# Sheet1.net
KiCad netlist of a schematic drawn in Altium Designer
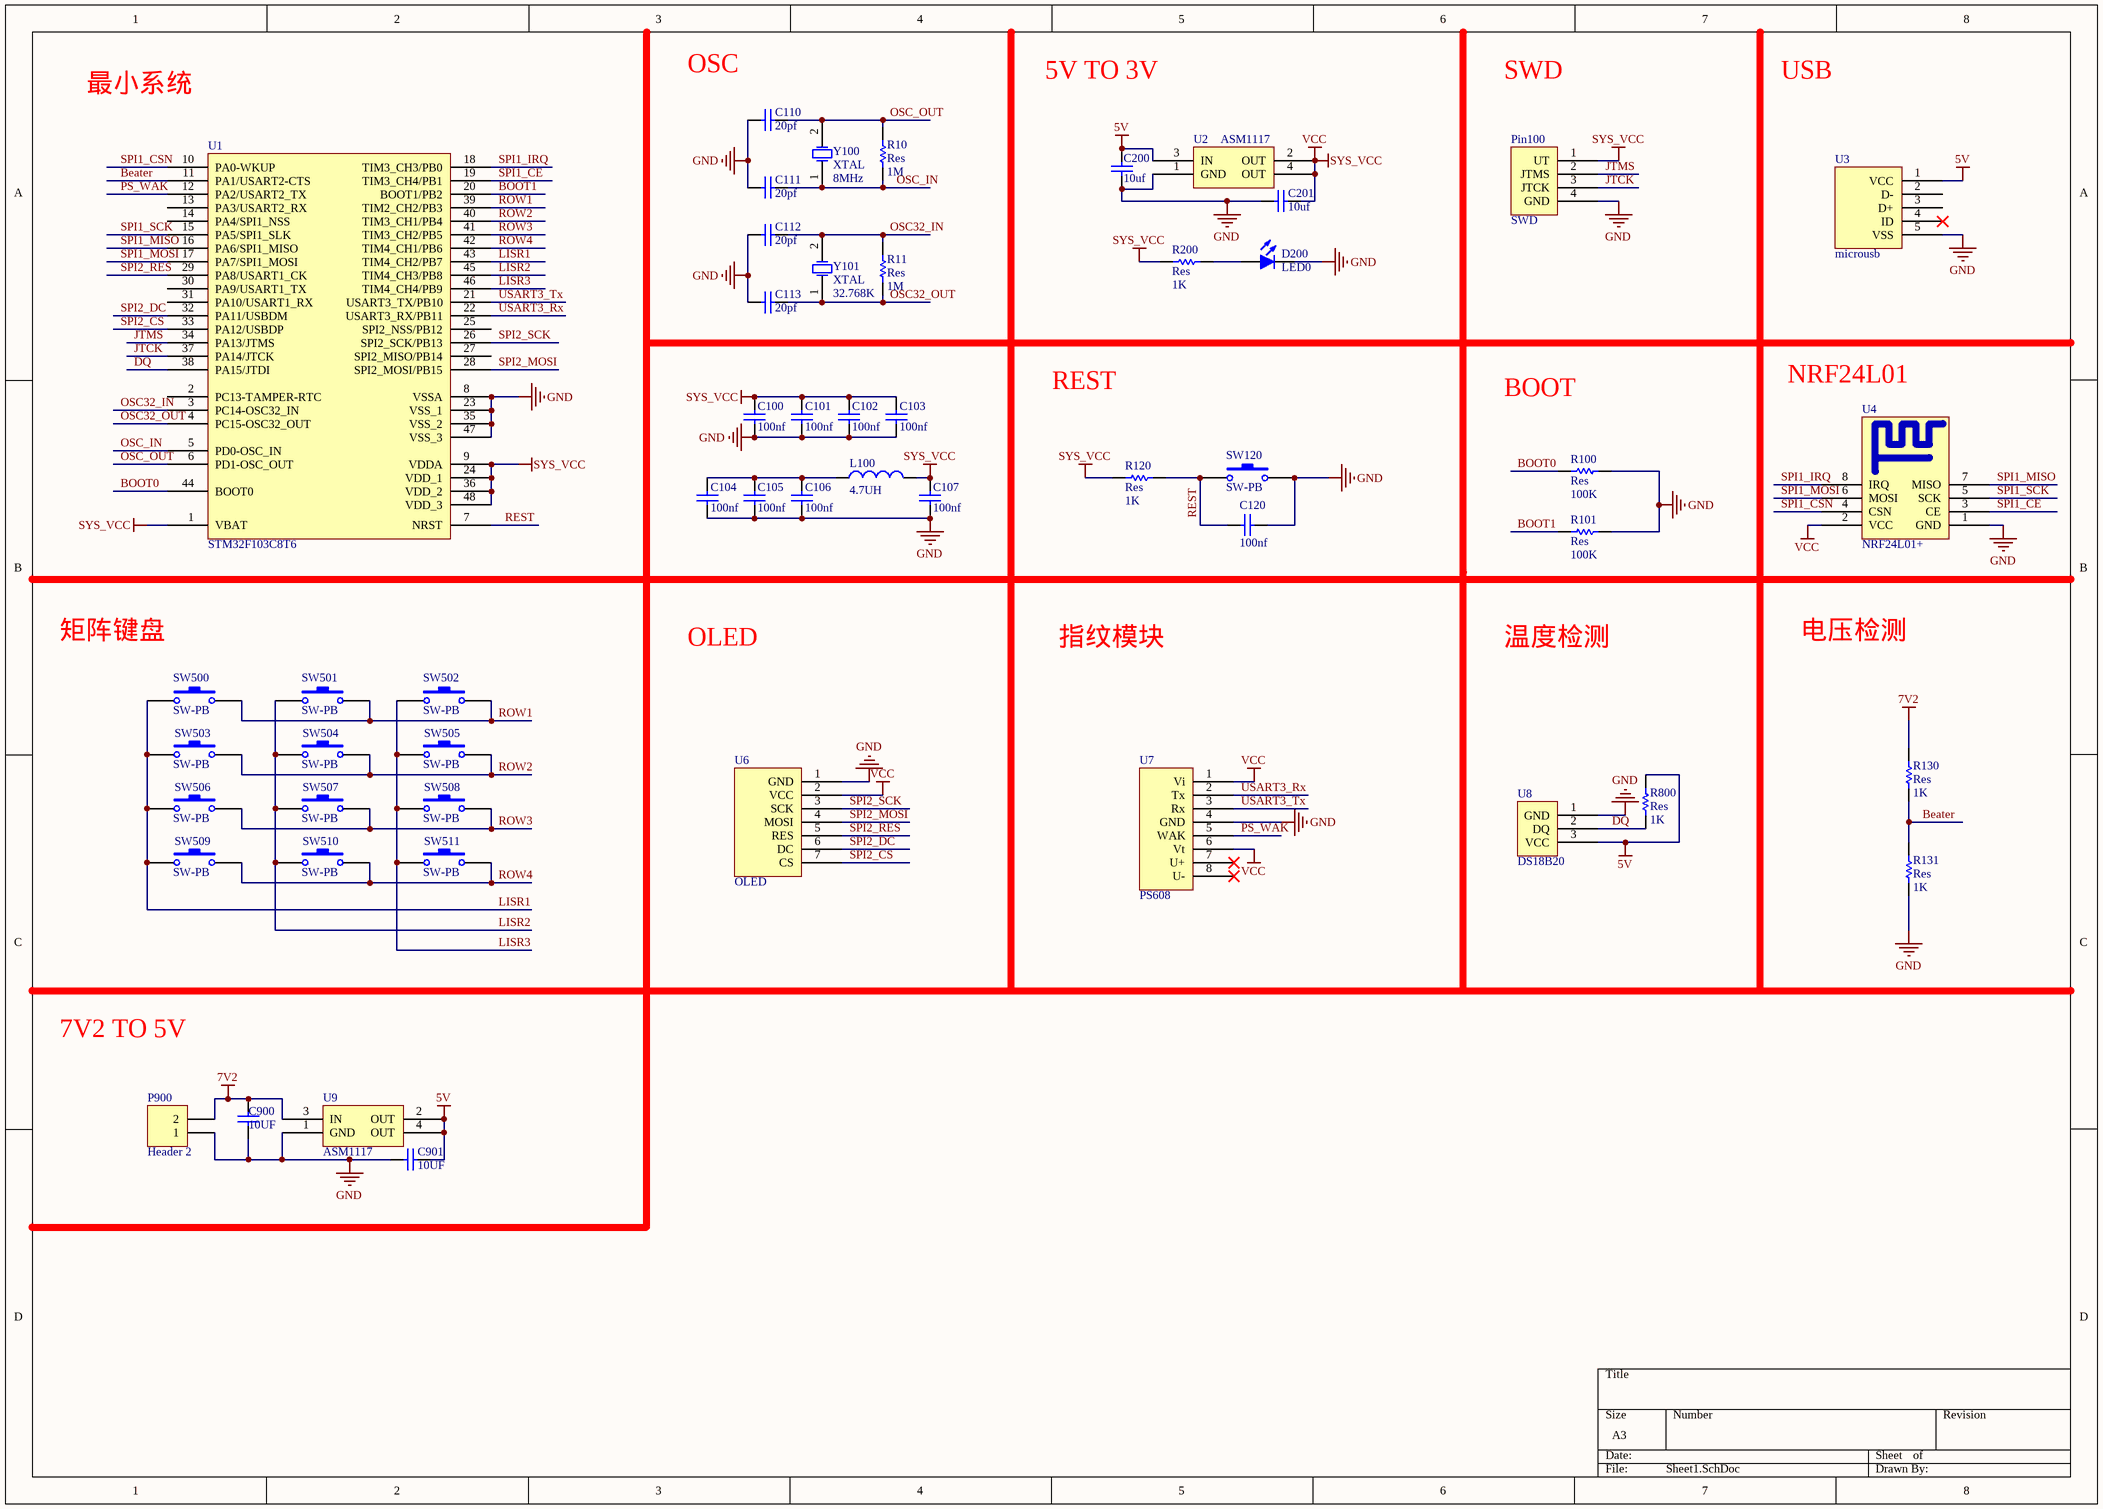
[diagram p0: Sheet1.SchDoc]

(export (version "E")
  (design (tool "Eeschema 10.0.6"))
  (components
    (comp (ref "C100")
      (value "100nf")
      (footprint "0805")
      (description "0805贴片电容")
      (libsource (lib "myintlib") (part "Cap"))
    )
    (comp (ref "C101")
      (value "100nf")
      (footprint "0805")
      (description "0805贴片电容")
      (libsource (lib "myintlib") (part "Cap"))
    )
    (comp (ref "C102")
      (value "100nf")
      (footprint "0805")
      (description "0805贴片电容")
      (libsource (lib "myintlib") (part "Cap"))
    )
    (comp (ref "C103")
      (value "100nf")
      (footprint "0805")
      (description "0805贴片电容")
      (libsource (lib "myintlib") (part "Cap"))
    )
    (comp (ref "C104")
      (value "100nf")
      (footprint "0805")
      (description "0805贴片电容")
      (libsource (lib "myintlib") (part "Cap"))
    )
    (comp (ref "C105")
      (value "100nf")
      (footprint "0805")
      (description "0805贴片电容")
      (libsource (lib "myintlib") (part "Cap"))
    )
    (comp (ref "C106")
      (value "100nf")
      (footprint "0805")
      (description "0805贴片电容")
      (libsource (lib "myintlib") (part "Cap"))
    )
    (comp (ref "C107")
      (value "100nf")
      (footprint "0805")
      (description "0805贴片电容")
      (libsource (lib "myintlib") (part "Cap"))
    )
    (comp (ref "C110")
      (value "20pf")
      (footprint "0805")
      (description "0805贴片电容")
      (libsource (lib "myintlib") (part "Cap"))
    )
    (comp (ref "C111")
      (value "20pf")
      (footprint "0805")
      (description "0805贴片电容")
      (libsource (lib "myintlib") (part "Cap"))
    )
    (comp (ref "C112")
      (value "20pf")
      (footprint "0805")
      (description "0805贴片电容")
      (libsource (lib "myintlib") (part "Cap"))
    )
    (comp (ref "C113")
      (value "20pf")
      (footprint "0805")
      (description "0805贴片电容")
      (libsource (lib "myintlib") (part "Cap"))
    )
    (comp (ref "C120")
      (value "100nf")
      (footprint "Cap0805")
      (description "0805贴片电容")
      (libsource (lib "myintlib") (part "Cap"))
    )
    (comp (ref "C200")
      (value "10uf")
      (footprint "0805")
      (description "0805贴片电容")
      (libsource (lib "myintlib") (part "Cap"))
    )
    (comp (ref "C201")
      (value "10uf")
      (footprint "0805")
      (description "0805贴片电容")
      (libsource (lib "myintlib") (part "Cap"))
    )
    (comp (ref "C900")
      (value "10UF")
      (footprint "Cap0805")
      (description "0805贴片电容")
      (libsource (lib "myintlib") (part "Cap"))
    )
    (comp (ref "C901")
      (value "10UF")
      (footprint "Cap0805")
      (description "0805贴片电容")
      (libsource (lib "myintlib") (part "Cap"))
    )
    (comp (ref "D200")
      (value "LED0")
      (footprint "LED-0805")
      (description "0805贴片LED灯")
      (libsource (lib "myintlib") (part "LED0"))
    )
    (comp (ref "L100")
      (value "4.7UH")
      (footprint "0805")
      (description "Inductor")
      (fields (field (name "PUBLISHER") "Altium Limited"))
      (libsource (lib "Miscellaneous Devices") (part "Inductor"))
    )
    (comp (ref "P900")
      (value "Header 2")
      (footprint "DC003")
      (description "Header, 2-Pin")
      (fields (field (name "PUBLISHER") "Altium Limited"))
      (libsource (lib "Miscellaneous Connectors") (part "Header 2"))
    )
    (comp (ref "Pin100")
      (value "SWD")
      (footprint "HDR1X4")
      (description "SWD下载端口")
      (libsource (lib "myintlib") (part "SWD"))
    )
    (comp (ref "R10")
      (value "Res")
      (footprint "0805")
      (description "0805贴片电阻")
      (fields (field (name "VAULE") "1M"))
      (libsource (lib "myintlib") (part "Res"))
    )
    (comp (ref "R11")
      (value "Res")
      (footprint "0805")
      (description "0805贴片电阻")
      (fields (field (name "VAULE") "1M"))
      (libsource (lib "myintlib") (part "Res"))
    )
    (comp (ref "R100")
      (value "Res")
      (footprint "0805")
      (description "0805贴片电阻")
      (fields (field (name "VAULE") "100K"))
      (libsource (lib "myintlib") (part "Res"))
    )
    (comp (ref "R101")
      (value "Res")
      (footprint "0805")
      (description "0805贴片电阻")
      (fields (field (name "VAULE") "100K"))
      (libsource (lib "myintlib") (part "Res"))
    )
    (comp (ref "R120")
      (value "Res")
      (footprint "0805")
      (description "0805贴片电阻")
      (fields (field (name "VAULE") "1K"))
      (libsource (lib "myintlib") (part "Res"))
    )
    (comp (ref "R130")
      (value "Res")
      (footprint "0805")
      (description "0805贴片电阻")
      (fields (field (name "VAULE") "1K"))
      (libsource (lib "myintlib") (part "Res"))
    )
    (comp (ref "R131")
      (value "Res")
      (footprint "0805")
      (description "0805贴片电阻")
      (fields (field (name "VAULE") "1K"))
      (libsource (lib "myintlib") (part "Res"))
    )
    (comp (ref "R200")
      (value "Res")
      (footprint "0805")
      (description "0805贴片电阻")
      (fields (field (name "VAULE") "1K"))
      (libsource (lib "myintlib") (part "Res"))
    )
    (comp (ref "R800")
      (value "Res")
      (footprint "0805")
      (description "0805贴片电阻")
      (fields (field (name "VAULE") "1K"))
      (libsource (lib "myintlib") (part "Res"))
    )
    (comp (ref "SW120")
      (value "SW-PB")
      (footprint "SW-PB")
      (description "贴片按键")
      (libsource (lib "myintlib") (part "SW-PB"))
    )
    (comp (ref "SW500")
      (value "SW-PB")
      (footprint "SW-PB")
      (description "贴片按键")
      (libsource (lib "myintlib") (part "SW-PB"))
    )
    (comp (ref "SW501")
      (value "SW-PB")
      (footprint "SW-PB")
      (description "贴片按键")
      (libsource (lib "myintlib") (part "SW-PB"))
    )
    (comp (ref "SW502")
      (value "SW-PB")
      (footprint "SW-PB")
      (description "贴片按键")
      (libsource (lib "myintlib") (part "SW-PB"))
    )
    (comp (ref "SW503")
      (value "SW-PB")
      (footprint "SW-PB")
      (description "贴片按键")
      (libsource (lib "myintlib") (part "SW-PB"))
    )
    (comp (ref "SW504")
      (value "SW-PB")
      (footprint "SW-PB")
      (description "贴片按键")
      (libsource (lib "myintlib") (part "SW-PB"))
    )
    (comp (ref "SW505")
      (value "SW-PB")
      (footprint "SW-PB")
      (description "贴片按键")
      (libsource (lib "myintlib") (part "SW-PB"))
    )
    (comp (ref "SW506")
      (value "SW-PB")
      (footprint "SW-PB")
      (description "贴片按键")
      (libsource (lib "myintlib") (part "SW-PB"))
    )
    (comp (ref "SW507")
      (value "SW-PB")
      (footprint "SW-PB")
      (description "贴片按键")
      (libsource (lib "myintlib") (part "SW-PB"))
    )
    (comp (ref "SW508")
      (value "SW-PB")
      (footprint "SW-PB")
      (description "贴片按键")
      (libsource (lib "myintlib") (part "SW-PB"))
    )
    (comp (ref "SW509")
      (value "SW-PB")
      (footprint "SW-PB")
      (description "贴片按键")
      (libsource (lib "myintlib") (part "SW-PB"))
    )
    (comp (ref "SW510")
      (value "SW-PB")
      (footprint "SW-PB")
      (description "贴片按键")
      (libsource (lib "myintlib") (part "SW-PB"))
    )
    (comp (ref "SW511")
      (value "SW-PB")
      (footprint "SW-PB")
      (description "贴片按键")
      (libsource (lib "myintlib") (part "SW-PB"))
    )
    (comp (ref "U1")
      (value "STM32F103C8T6")
      (footprint "LQFP-48")
      (description "Cortex-M3内核单片机")
      (libsource (lib "myintlib") (part "STM32F103C8T6"))
    )
    (comp (ref "U2")
      (value "ASM1117")
      (footprint "SOT-223")
      (description "线性稳压芯片")
      (libsource (lib "myintlib") (part "ASM1117"))
    )
    (comp (ref "U3") (value "microusb") (footprint "microusb") (libsource (lib "myintlib") (part "microusb")))
    (comp (ref "U4")
      (value "NRF24L01+")
      (footprint "DIP8NRF")
      (description "直插式NRF")
      (libsource (lib "myintlib") (part "NRF24L01+"))
    )
    (comp (ref "U6") (value "OLED") (footprint "OLED") (libsource (lib "myintlib") (part "OLED")))
    (comp (ref "U7")
      (value "PS608")
      (footprint "HDR1X8")
      (description "指纹模块")
      (libsource (lib "myintlib") (part "PS608"))
    )
    (comp (ref "U8")
      (value "DS18B20")
      (footprint "TO-92")
      (description "温度传感器")
      (libsource (lib "myintlib") (part "DS18B20"))
    )
    (comp (ref "U9")
      (value "ASM1117")
      (footprint "SOT-223")
      (description "线性稳压芯片")
      (libsource (lib "myintlib") (part "ASM1117"))
    )
    (comp (ref "Y100")
      (value "XTAL")
      (footprint "X-HC49U")
      (description "无源晶振")
      (fields (field (name "ALTIUM_UNNAMED_1") "8MHz"))
      (libsource (lib "myintlib") (part "XTAL"))
    )
    (comp (ref "Y101")
      (value "XTAL")
      (footprint "308晶振")
      (description "无源晶振")
      (fields (field (name "ALTIUM_UNNAMED_1") "32.768K"))
      (libsource (lib "myintlib") (part "XTAL"))
    )
  )
  (nets
    (net (code "1") (name "/BOOT0") (class "Default")
      (node (ref "R100") (pin "1") (pinfunction "1_1") (pintype "passive"))
      (node (ref "U1") (pin "44") (pinfunction "BOOT0_44") (pintype "passive"))
    )
    (net (code "2") (name "/BOOT1") (class "Default")
      (node (ref "R101") (pin "1") (pinfunction "1_1") (pintype "passive"))
      (node (ref "U1") (pin "20") (pinfunction "BOOT1/PB2_20") (pintype "passive"))
    )
    (net (code "3") (name "/Beater") (class "Default")
      (node (ref "R130") (pin "1") (pinfunction "1_1") (pintype "passive"))
      (node (ref "R131") (pin "2") (pinfunction "2_2") (pintype "passive"))
      (node (ref "U1") (pin "11") (pinfunction "PA1/USART2-CTS_11") (pintype "passive"))
    )
    (net (code "4") (name "/DQ") (class "Default")
      (node (ref "R800") (pin "1") (pinfunction "1_1") (pintype "passive"))
      (node (ref "U1") (pin "38") (pinfunction "PA15/JTDI_38") (pintype "passive"))
      (node (ref "U8") (pin "2") (pinfunction "DQ_2") (pintype "passive"))
    )
    (net (code "5") (name "/JTCK") (class "Default")
      (node (ref "Pin100") (pin "3") (pinfunction "JTCK_3") (pintype "power_in"))
      (node (ref "U1") (pin "37") (pinfunction "PA14/JTCK_37") (pintype "passive"))
    )
    (net (code "6") (name "/JTMS") (class "Default")
      (node (ref "Pin100") (pin "2") (pinfunction "JTMS_2") (pintype "power_in"))
      (node (ref "U1") (pin "34") (pinfunction "PA13/JTMS_34") (pintype "passive"))
    )
    (net (code "7") (name "/LISR1") (class "Default")
      (node (ref "SW500") (pin "1") (pinfunction "1_1") (pintype "passive"))
      (node (ref "SW503") (pin "1") (pinfunction "1_1") (pintype "passive"))
      (node (ref "SW506") (pin "1") (pinfunction "1_1") (pintype "passive"))
      (node (ref "SW509") (pin "1") (pinfunction "1_1") (pintype "passive"))
      (node (ref "U1") (pin "43") (pinfunction "TIM4_CH2/PB7_43") (pintype "passive"))
    )
    (net (code "8") (name "/LISR2") (class "Default")
      (node (ref "SW501") (pin "1") (pinfunction "1_1") (pintype "passive"))
      (node (ref "SW504") (pin "1") (pinfunction "1_1") (pintype "passive"))
      (node (ref "SW507") (pin "1") (pinfunction "1_1") (pintype "passive"))
      (node (ref "SW510") (pin "1") (pinfunction "1_1") (pintype "passive"))
      (node (ref "U1") (pin "45") (pinfunction "TIM4_CH3/PB8_45") (pintype "passive"))
    )
    (net (code "9") (name "/LISR3") (class "Default")
      (node (ref "SW502") (pin "1") (pinfunction "1_1") (pintype "passive"))
      (node (ref "SW505") (pin "1") (pinfunction "1_1") (pintype "passive"))
      (node (ref "SW508") (pin "1") (pinfunction "1_1") (pintype "passive"))
      (node (ref "SW511") (pin "1") (pinfunction "1_1") (pintype "passive"))
      (node (ref "U1") (pin "46") (pinfunction "TIM4_CH4/PB9_46") (pintype "passive"))
    )
    (net (code "10") (name "/OSC32_IN") (class "Default")
      (node (ref "C112") (pin "1") (pinfunction "1_1") (pintype "passive"))
      (node (ref "R11") (pin "2") (pinfunction "2_2") (pintype "passive"))
      (node (ref "U1") (pin "3") (pinfunction "PC14-OSC32_IN_3") (pintype "passive"))
      (node (ref "Y101") (pin "2") (pinfunction "OSC2_2") (pintype "passive"))
    )
    (net (code "11") (name "/OSC32_OUT") (class "Default")
      (node (ref "C113") (pin "1") (pinfunction "1_1") (pintype "passive"))
      (node (ref "R11") (pin "1") (pinfunction "1_1") (pintype "passive"))
      (node (ref "U1") (pin "4") (pinfunction "PC15-OSC32_OUT_4") (pintype "passive"))
      (node (ref "Y101") (pin "1") (pinfunction "OSC1_1") (pintype "passive"))
    )
    (net (code "12") (name "/OSC_IN") (class "Default")
      (node (ref "C111") (pin "1") (pinfunction "1_1") (pintype "passive"))
      (node (ref "R10") (pin "1") (pinfunction "1_1") (pintype "passive"))
      (node (ref "U1") (pin "5") (pinfunction "PD0-OSC_IN_5") (pintype "passive"))
      (node (ref "Y100") (pin "1") (pinfunction "OSC1_1") (pintype "passive"))
    )
    (net (code "13") (name "/OSC_OUT") (class "Default")
      (node (ref "C110") (pin "1") (pinfunction "1_1") (pintype "passive"))
      (node (ref "R10") (pin "2") (pinfunction "2_2") (pintype "passive"))
      (node (ref "U1") (pin "6") (pinfunction "PD1-OSC_OUT_6") (pintype "passive"))
      (node (ref "Y100") (pin "2") (pinfunction "OSC2_2") (pintype "passive"))
    )
    (net (code "14") (name "/PS_WAK") (class "Default")
      (node (ref "U1") (pin "12") (pinfunction "PA2/USART2_TX_12") (pintype "passive"))
      (node (ref "U7") (pin "5") (pinfunction "WAK_5") (pintype "passive"))
    )
    (net (code "15") (name "/REST") (class "Default")
      (node (ref "C120") (pin "1") (pinfunction "1_1") (pintype "passive"))
      (node (ref "R120") (pin "2") (pinfunction "2_2") (pintype "passive"))
      (node (ref "SW120") (pin "1") (pinfunction "1_1") (pintype "passive"))
      (node (ref "U1") (pin "7") (pinfunction "NRST_7") (pintype "passive"))
    )
    (net (code "16") (name "/ROW1") (class "Default")
      (node (ref "SW500") (pin "2") (pinfunction "2_2") (pintype "passive"))
      (node (ref "SW501") (pin "2") (pinfunction "2_2") (pintype "passive"))
      (node (ref "SW502") (pin "2") (pinfunction "2_2") (pintype "passive"))
      (node (ref "U1") (pin "39") (pinfunction "TIM2_CH2/PB3_39") (pintype "passive"))
    )
    (net (code "17") (name "/ROW2") (class "Default")
      (node (ref "SW503") (pin "2") (pinfunction "2_2") (pintype "passive"))
      (node (ref "SW504") (pin "2") (pinfunction "2_2") (pintype "passive"))
      (node (ref "SW505") (pin "2") (pinfunction "2_2") (pintype "passive"))
      (node (ref "U1") (pin "40") (pinfunction "TIM3_CH1/PB4_40") (pintype "passive"))
    )
    (net (code "18") (name "/ROW3") (class "Default")
      (node (ref "SW506") (pin "2") (pinfunction "2_2") (pintype "passive"))
      (node (ref "SW507") (pin "2") (pinfunction "2_2") (pintype "passive"))
      (node (ref "SW508") (pin "2") (pinfunction "2_2") (pintype "passive"))
      (node (ref "U1") (pin "41") (pinfunction "TIM3_CH2/PB5_41") (pintype "passive"))
    )
    (net (code "19") (name "/ROW4") (class "Default")
      (node (ref "SW509") (pin "2") (pinfunction "2_2") (pintype "passive"))
      (node (ref "SW510") (pin "2") (pinfunction "2_2") (pintype "passive"))
      (node (ref "SW511") (pin "2") (pinfunction "2_2") (pintype "passive"))
      (node (ref "U1") (pin "42") (pinfunction "TIM4_CH1/PB6_42") (pintype "passive"))
    )
    (net (code "20") (name "/SPI1_CE") (class "Default")
      (node (ref "U1") (pin "19") (pinfunction "TIM3_CH4/PB1_19") (pintype "passive"))
      (node (ref "U4") (pin "3") (pinfunction "CE_3") (pintype "passive"))
    )
    (net (code "21") (name "/SPI1_CSN") (class "Default")
      (node (ref "U1") (pin "10") (pinfunction "PA0-WKUP_10") (pintype "passive"))
      (node (ref "U4") (pin "4") (pinfunction "CSN_4") (pintype "passive"))
    )
    (net (code "22") (name "/SPI1_IRQ") (class "Default")
      (node (ref "U1") (pin "18") (pinfunction "TIM3_CH3/PB0_18") (pintype "passive"))
      (node (ref "U4") (pin "8") (pinfunction "IRQ_8") (pintype "passive"))
    )
    (net (code "23") (name "/SPI1_MISO") (class "Default")
      (node (ref "U1") (pin "16") (pinfunction "PA6/SPI1_MISO_16") (pintype "passive"))
      (node (ref "U4") (pin "7") (pinfunction "MISO_7") (pintype "passive"))
    )
    (net (code "24") (name "/SPI1_MOSI") (class "Default")
      (node (ref "U1") (pin "17") (pinfunction "PA7/SPI1_MOSI_17") (pintype "passive"))
      (node (ref "U4") (pin "6") (pinfunction "MOSI_6") (pintype "passive"))
    )
    (net (code "25") (name "/SPI1_SCK") (class "Default")
      (node (ref "U1") (pin "15") (pinfunction "PA5/SPI1_SLK_15") (pintype "passive"))
      (node (ref "U4") (pin "5") (pinfunction "SCK_5") (pintype "passive"))
    )
    (net (code "26") (name "/SPI2_CS") (class "Default")
      (node (ref "U1") (pin "33") (pinfunction "PA12/USBDP_33") (pintype "passive"))
      (node (ref "U6") (pin "7") (pinfunction "CS_7") (pintype "passive"))
    )
    (net (code "27") (name "/SPI2_DC") (class "Default")
      (node (ref "U1") (pin "32") (pinfunction "PA11/USBDM_32") (pintype "passive"))
      (node (ref "U6") (pin "6") (pinfunction "DC_6") (pintype "passive"))
    )
    (net (code "28") (name "/SPI2_MOSI") (class "Default")
      (node (ref "U1") (pin "28") (pinfunction "SPI2_MOSI/PB15_28") (pintype "passive"))
      (node (ref "U6") (pin "4") (pinfunction "MOSI_4") (pintype "passive"))
    )
    (net (code "29") (name "/SPI2_RES") (class "Default")
      (node (ref "U1") (pin "29") (pinfunction "PA8/USART1_CK_29") (pintype "passive"))
      (node (ref "U6") (pin "5") (pinfunction "RES_5") (pintype "passive"))
    )
    (net (code "30") (name "/SPI2_SCK") (class "Default")
      (node (ref "U1") (pin "26") (pinfunction "SPI2_SCK/PB13_26") (pintype "passive"))
      (node (ref "U6") (pin "3") (pinfunction "SCK_3") (pintype "passive"))
    )
    (net (code "31") (name "/USART3_Rx") (class "Default")
      (node (ref "U1") (pin "22") (pinfunction "USART3_RX/PB11_22") (pintype "passive"))
      (node (ref "U7") (pin "2") (pinfunction "Tx_2") (pintype "passive"))
    )
    (net (code "32") (name "/USART3_Tx") (class "Default")
      (node (ref "U1") (pin "21") (pinfunction "USART3_TX/PB10_21") (pintype "passive"))
      (node (ref "U7") (pin "3") (pinfunction "Rx_3") (pintype "passive"))
    )
    (net (code "33") (name "5V") (class "Default")
      (node (ref "C200") (pin "2") (pinfunction "2_2") (pintype "passive"))
      (node (ref "C901") (pin "1") (pinfunction "1_1") (pintype "passive"))
      (node (ref "R800") (pin "2") (pinfunction "2_2") (pintype "passive"))
      (node (ref "U2") (pin "3") (pinfunction "IN_3") (pintype "passive"))
      (node (ref "U3") (pin "1") (pinfunction "VCC_1") (pintype "passive"))
      (node (ref "U8") (pin "3") (pinfunction "VCC_3") (pintype "passive"))
      (node (ref "U9") (pin "2") (pinfunction "OUT_2") (pintype "passive"))
      (node (ref "U9") (pin "4") (pinfunction "OUT_4") (pintype "passive"))
    )
    (net (code "34") (name "7V2") (class "Default")
      (node (ref "C900") (pin "2") (pinfunction "2_2") (pintype "passive"))
      (node (ref "P900") (pin "2") (pinfunction "2_2") (pintype "passive"))
      (node (ref "R130") (pin "2") (pinfunction "2_2") (pintype "passive"))
      (node (ref "U9") (pin "3") (pinfunction "IN_3") (pintype "passive"))
    )
    (net (code "35") (name "GND") (class "Default")
      (node (ref "C100") (pin "1") (pinfunction "1_1") (pintype "passive"))
      (node (ref "C101") (pin "1") (pinfunction "1_1") (pintype "passive"))
      (node (ref "C102") (pin "1") (pinfunction "1_1") (pintype "passive"))
      (node (ref "C103") (pin "1") (pinfunction "1_1") (pintype "passive"))
      (node (ref "C104") (pin "1") (pinfunction "1_1") (pintype "passive"))
      (node (ref "C105") (pin "1") (pinfunction "1_1") (pintype "passive"))
      (node (ref "C106") (pin "1") (pinfunction "1_1") (pintype "passive"))
      (node (ref "C107") (pin "1") (pinfunction "1_1") (pintype "passive"))
      (node (ref "C110") (pin "2") (pinfunction "2_2") (pintype "passive"))
      (node (ref "C111") (pin "2") (pinfunction "2_2") (pintype "passive"))
      (node (ref "C112") (pin "2") (pinfunction "2_2") (pintype "passive"))
      (node (ref "C113") (pin "2") (pinfunction "2_2") (pintype "passive"))
      (node (ref "C120") (pin "2") (pinfunction "2_2") (pintype "passive"))
      (node (ref "C200") (pin "1") (pinfunction "1_1") (pintype "passive"))
      (node (ref "C201") (pin "2") (pinfunction "2_2") (pintype "passive"))
      (node (ref "C900") (pin "1") (pinfunction "1_1") (pintype "passive"))
      (node (ref "C901") (pin "2") (pinfunction "2_2") (pintype "passive"))
      (node (ref "D200") (pin "2") (pinfunction "K_2") (pintype "passive"))
      (node (ref "P900") (pin "1") (pinfunction "1_1") (pintype "passive"))
      (node (ref "Pin100") (pin "4") (pinfunction "GND_4") (pintype "power_in"))
      (node (ref "R100") (pin "2") (pinfunction "2_2") (pintype "passive"))
      (node (ref "R101") (pin "2") (pinfunction "2_2") (pintype "passive"))
      (node (ref "R131") (pin "1") (pinfunction "1_1") (pintype "passive"))
      (node (ref "SW120") (pin "2") (pinfunction "2_2") (pintype "passive"))
      (node (ref "U1") (pin "23") (pinfunction "VSS_1_23") (pintype "passive"))
      (node (ref "U1") (pin "35") (pinfunction "VSS_2_35") (pintype "passive"))
      (node (ref "U1") (pin "47") (pinfunction "VSS_3_47") (pintype "passive"))
      (node (ref "U1") (pin "8") (pinfunction "VSSA_8") (pintype "passive"))
      (node (ref "U2") (pin "1") (pinfunction "GND_1") (pintype "passive"))
      (node (ref "U3") (pin "5") (pinfunction "VSS_5") (pintype "passive"))
      (node (ref "U4") (pin "1") (pinfunction "GND_1") (pintype "passive"))
      (node (ref "U6") (pin "1") (pinfunction "GND_1") (pintype "passive"))
      (node (ref "U7") (pin "4") (pinfunction "GND_4") (pintype "passive"))
      (node (ref "U8") (pin "1") (pinfunction "GND_1") (pintype "passive"))
      (node (ref "U9") (pin "1") (pinfunction "GND_1") (pintype "passive"))
    )
    (net (code "36") (name "Net-(C104-Pad2)") (class "Default")
      (node (ref "C104") (pin "2") (pinfunction "2_2") (pintype "passive"))
      (node (ref "C105") (pin "2") (pinfunction "2_2") (pintype "passive"))
      (node (ref "C106") (pin "2") (pinfunction "2_2") (pintype "passive"))
      (node (ref "L100") (pin "1") (pinfunction "1_1") (pintype "passive"))
    )
    (net (code "37") (name "Net-(D200-A)") (class "Default")
      (node (ref "D200") (pin "1") (pinfunction "A_1") (pintype "passive"))
      (node (ref "R200") (pin "2") (pinfunction "2_2") (pintype "passive"))
    )
    (net (code "38") (name "SYS_VCC") (class "Default")
      (node (ref "C100") (pin "2") (pinfunction "2_2") (pintype "passive"))
      (node (ref "C101") (pin "2") (pinfunction "2_2") (pintype "passive"))
      (node (ref "C102") (pin "2") (pinfunction "2_2") (pintype "passive"))
      (node (ref "C103") (pin "2") (pinfunction "2_2") (pintype "passive"))
      (node (ref "C107") (pin "2") (pinfunction "2_2") (pintype "passive"))
      (node (ref "C201") (pin "1") (pinfunction "1_1") (pintype "passive"))
      (node (ref "L100") (pin "2") (pinfunction "2_2") (pintype "passive"))
      (node (ref "Pin100") (pin "1") (pinfunction "UT_1") (pintype "power_in"))
      (node (ref "R120") (pin "1") (pinfunction "1_1") (pintype "passive"))
      (node (ref "R200") (pin "1") (pinfunction "1_1") (pintype "passive"))
      (node (ref "U1") (pin "1") (pinfunction "VBAT_1") (pintype "passive"))
      (node (ref "U1") (pin "24") (pinfunction "VDD_1_24") (pintype "passive"))
      (node (ref "U1") (pin "36") (pinfunction "VDD_2_36") (pintype "passive"))
      (node (ref "U1") (pin "48") (pinfunction "VDD_3_48") (pintype "passive"))
      (node (ref "U1") (pin "9") (pinfunction "VDDA_9") (pintype "passive"))
      (node (ref "U2") (pin "2") (pinfunction "OUT_2") (pintype "passive"))
      (node (ref "U2") (pin "4") (pinfunction "OUT_4") (pintype "passive"))
      (node (ref "U4") (pin "2") (pinfunction "VCC_2") (pintype "passive"))
      (node (ref "U6") (pin "2") (pinfunction "VCC_2") (pintype "passive"))
      (node (ref "U7") (pin "1") (pinfunction "Vi_1") (pintype "passive"))
      (node (ref "U7") (pin "6") (pinfunction "Vt_6") (pintype "passive"))
    )
    (net (code "39") (name "unconnected-(U1-PA3{slash}USART2_RX-Pad13)") (class "Default")
      (node (ref "U1") (pin "13") (pinfunction "PA3/USART2_RX_13") (pintype "passive"))
    )
    (net (code "40") (name "unconnected-(U1-PA4{slash}SPI1_NSS-Pad14)") (class "Default")
      (node (ref "U1") (pin "14") (pinfunction "PA4/SPI1_NSS_14") (pintype "passive"))
    )
    (net (code "41") (name "unconnected-(U1-PA9{slash}USART1_TX-Pad30)") (class "Default")
      (node (ref "U1") (pin "30") (pinfunction "PA9/USART1_TX_30") (pintype "passive"))
    )
    (net (code "42") (name "unconnected-(U1-PA10{slash}USART1_RX-Pad31)") (class "Default")
      (node (ref "U1") (pin "31") (pinfunction "PA10/USART1_RX_31") (pintype "passive"))
    )
    (net (code "43") (name "unconnected-(U1-PC13-TAMPER-RTC-Pad2)") (class "Default")
      (node (ref "U1") (pin "2") (pinfunction "PC13-TAMPER-RTC_2") (pintype "passive"))
    )
    (net (code "44") (name "unconnected-(U1-SPI2_MISO{slash}PB14-Pad27)") (class "Default")
      (node (ref "U1") (pin "27") (pinfunction "SPI2_MISO/PB14_27") (pintype "passive"))
    )
    (net (code "45") (name "unconnected-(U1-SPI2_NSS{slash}PB12-Pad25)") (class "Default")
      (node (ref "U1") (pin "25") (pinfunction "SPI2_NSS/PB12_25") (pintype "passive"))
    )
    (net (code "46") (name "unconnected-(U3-D+-Pad3)") (class "Default")
      (node (ref "U3") (pin "3") (pinfunction "D+_3") (pintype "passive"))
    )
    (net (code "47") (name "unconnected-(U3-D--Pad2)") (class "Default")
      (node (ref "U3") (pin "2") (pinfunction "D-_2") (pintype "passive"))
    )
    (net (code "48") (name "unconnected-(U3-ID-Pad4)") (class "Default")
      (node (ref "U3") (pin "4") (pinfunction "ID_4") (pintype "passive+no_connect"))
    )
    (net (code "49") (name "unconnected-(U7-U+-Pad7)") (class "Default")
      (node (ref "U7") (pin "7") (pinfunction "U+_7") (pintype "passive+no_connect"))
    )
    (net (code "50") (name "unconnected-(U7-U--Pad8)") (class "Default")
      (node (ref "U7") (pin "8") (pinfunction "U-_8") (pintype "passive+no_connect"))
    )
  )
)
